# connectors.net
KiCad netlist of a schematic drawn in Altium Designer
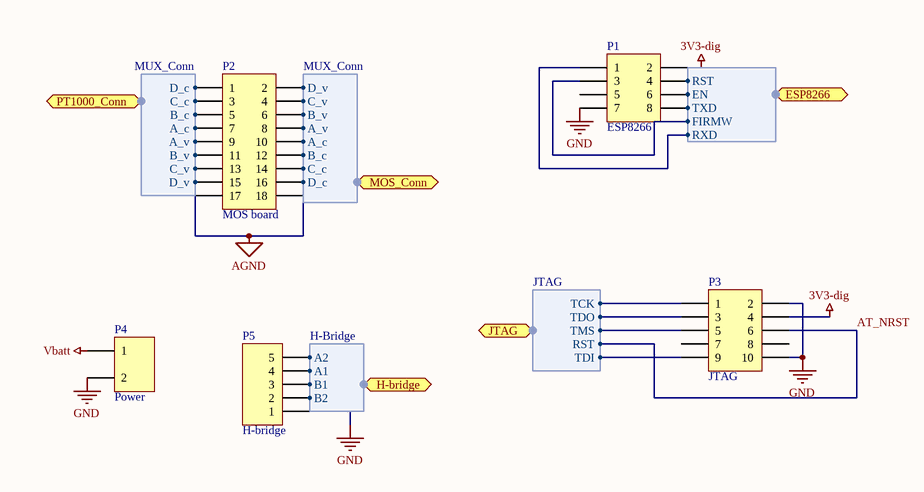
[diagram p0: connectors.SchDoc]

(export (version "E")
  (design (tool "Eeschema 10.0.6"))
  (components
    (comp (ref "P1")
      (value "ESP8266")
      (footprint "Header 2x4")
      (description "Header, 4-Pin, Dual row")
      (fields (field (name "PUBLISHER") "Altium Limited"))
      (libsource (lib "Miscellaneous Connectors") (part "Header 4X2"))
    )
    (comp (ref "P2")
      (value "MOS board")
      (footprint "Header 2x9")
      (description "Header, 9-Pin, Dual row")
      (fields (field (name "PUBLISHER") "Altium Limited"))
      (libsource (lib "Miscellaneous Connectors") (part "Header 9X2"))
    )
    (comp (ref "P3")
      (value "JTAG")
      (footprint "Header 2x5")
      (description "Header, 5-Pin, Dual row")
      (fields (field (name "PUBLISHER") "Altium Limited"))
      (libsource (lib "Miscellaneous Connectors") (part "Header 5X2"))
    )
    (comp (ref "P4")
      (value "Power")
      (footprint "Header 1x3")
      (description "Header, 3-Pin")
      (fields (field (name "PUBLISHER") "Altium Limited"))
      (libsource (lib "Miscellaneous Connectors") (part "Header 3"))
    )
    (comp (ref "P5")
      (value "H-bridge")
      (footprint "Header 1x5")
      (description "Header, 5-Pin")
      (fields (field (name "PUBLISHER") "Altium Limited"))
      (libsource (lib "Miscellaneous Connectors") (part "Header 5"))
    )
  )
  (nets
    (net (code "4") (name "/A1") (class "Default")
      (node (ref "P5") (pin "4") (pinfunction "4_4") (pintype "passive"))
    )
    (net (code "5") (name "/A2") (class "Default")
      (node (ref "P5") (pin "5") (pinfunction "5_5") (pintype "passive"))
    )
    (net (code "6") (name "/AT_NRST") (class "Default")
      (node (ref "P3") (pin "6") (pinfunction "6_6") (pintype "passive"))
    )
    (net (code "7") (name "/B1") (class "Default")
      (node (ref "P5") (pin "3") (pinfunction "3_3") (pintype "passive"))
    )
    (net (code "8") (name "/B2") (class "Default")
      (node (ref "P5") (pin "2") (pinfunction "2_2") (pintype "passive"))
    )
    (net (code "9") (name "/EN") (class "Default")
      (node (ref "P1") (pin "6") (pinfunction "6_6") (pintype "passive"))
    )
    (net (code "10") (name "/FIRMW") (class "Default")
      (node (ref "P1") (pin "3") (pinfunction "3_3") (pintype "passive"))
    )
    (net (code "11") (name "/RXD") (class "Default")
      (node (ref "P1") (pin "1") (pinfunction "1_1") (pintype "passive"))
    )
    (net (code "12") (name "/TCK") (class "Default")
      (node (ref "P3") (pin "1") (pinfunction "1_1") (pintype "passive"))
    )
    (net (code "13") (name "/TDI") (class "Default")
      (node (ref "P3") (pin "9") (pinfunction "9_9") (pintype "passive"))
    )
    (net (code "14") (name "/TDO") (class "Default")
      (node (ref "P3") (pin "3") (pinfunction "3_3") (pintype "passive"))
    )
    (net (code "15") (name "/TMS") (class "Default")
      (node (ref "P3") (pin "5") (pinfunction "5_5") (pintype "passive"))
    )
    (net (code "16") (name "/TXD") (class "Default")
      (node (ref "P1") (pin "8") (pinfunction "8_8") (pintype "passive"))
    )
    (net (code "20") (name "3V3-dig") (class "Default")
      (node (ref "P1") (pin "2") (pinfunction "2_2") (pintype "passive"))
      (node (ref "P3") (pin "4") (pinfunction "4_4") (pintype "passive"))
    )
    (net (code "21") (name "AGND") (class "Default")
      (node (ref "P2") (pin "17") (pinfunction "17_17") (pintype "passive"))
      (node (ref "P2") (pin "18") (pinfunction "18_18") (pintype "passive"))
    )
    (net (code "22") (name "GND") (class "Default")
      (node (ref "P1") (pin "7") (pinfunction "7_7") (pintype "passive"))
      (node (ref "P3") (pin "10") (pinfunction "10_10") (pintype "passive"))
      (node (ref "P3") (pin "2") (pinfunction "2_2") (pintype "passive"))
      (node (ref "P4") (pin "3") (pinfunction "2_3") (pintype "passive"))
      (node (ref "P5") (pin "1") (pinfunction "1_1") (pintype "passive"))
    )
    (net (code "23") (name "Vbatt") (class "Default")
      (node (ref "P4") (pin "1") (pinfunction "1_1") (pintype "passive"))
    )
    (net (code "24") (name "unconnected-(P1-Pad4)") (class "Default")
      (node (ref "P1") (pin "4") (pinfunction "4_4") (pintype "passive"))
    )
    (net (code "25") (name "unconnected-(P1-Pad5)") (class "Default")
      (node (ref "P1") (pin "5") (pinfunction "5_5") (pintype "passive"))
    )
    (net (code "26") (name "unconnected-(P2-Pad1)") (class "Default")
      (node (ref "P2") (pin "1") (pinfunction "1_1") (pintype "passive"))
    )
    (net (code "27") (name "unconnected-(P2-Pad2)") (class "Default")
      (node (ref "P2") (pin "2") (pinfunction "2_2") (pintype "passive"))
    )
    (net (code "28") (name "unconnected-(P2-Pad3)") (class "Default")
      (node (ref "P2") (pin "3") (pinfunction "3_3") (pintype "passive"))
    )
    (net (code "29") (name "unconnected-(P2-Pad4)") (class "Default")
      (node (ref "P2") (pin "4") (pinfunction "4_4") (pintype "passive"))
    )
    (net (code "30") (name "unconnected-(P2-Pad5)") (class "Default")
      (node (ref "P2") (pin "5") (pinfunction "5_5") (pintype "passive"))
    )
    (net (code "31") (name "unconnected-(P2-Pad6)") (class "Default")
      (node (ref "P2") (pin "6") (pinfunction "6_6") (pintype "passive"))
    )
    (net (code "32") (name "unconnected-(P2-Pad7)") (class "Default")
      (node (ref "P2") (pin "7") (pinfunction "7_7") (pintype "passive"))
    )
    (net (code "33") (name "unconnected-(P2-Pad8)") (class "Default")
      (node (ref "P2") (pin "8") (pinfunction "8_8") (pintype "passive"))
    )
    (net (code "34") (name "unconnected-(P2-Pad9)") (class "Default")
      (node (ref "P2") (pin "9") (pinfunction "9_9") (pintype "passive"))
    )
    (net (code "35") (name "unconnected-(P2-Pad10)") (class "Default")
      (node (ref "P2") (pin "10") (pinfunction "10_10") (pintype "passive"))
    )
    (net (code "36") (name "unconnected-(P2-Pad11)") (class "Default")
      (node (ref "P2") (pin "11") (pinfunction "11_11") (pintype "passive"))
    )
    (net (code "37") (name "unconnected-(P2-Pad12)") (class "Default")
      (node (ref "P2") (pin "12") (pinfunction "12_12") (pintype "passive"))
    )
    (net (code "38") (name "unconnected-(P2-Pad13)") (class "Default")
      (node (ref "P2") (pin "13") (pinfunction "13_13") (pintype "passive"))
    )
    (net (code "39") (name "unconnected-(P2-Pad14)") (class "Default")
      (node (ref "P2") (pin "14") (pinfunction "14_14") (pintype "passive"))
    )
    (net (code "40") (name "unconnected-(P2-Pad15)") (class "Default")
      (node (ref "P2") (pin "15") (pinfunction "15_15") (pintype "passive"))
    )
    (net (code "41") (name "unconnected-(P2-Pad16)") (class "Default")
      (node (ref "P2") (pin "16") (pinfunction "16_16") (pintype "passive"))
    )
    (net (code "42") (name "unconnected-(P3-Pad7)") (class "Default")
      (node (ref "P3") (pin "7") (pinfunction "7_7") (pintype "passive"))
    )
    (net (code "43") (name "unconnected-(P3-Pad8)") (class "Default")
      (node (ref "P3") (pin "8") (pinfunction "8_8") (pintype "passive"))
    )
    (net (code "44") (name "unconnected-(P4-Pad2)") (class "Default")
      (node (ref "P4") (pin "2") (pinfunction "2_2") (pintype "passive"))
    )
  )
)
